# Heizstabsteuerung.net
KiCad netlist of a schematic drawn in EAGLE
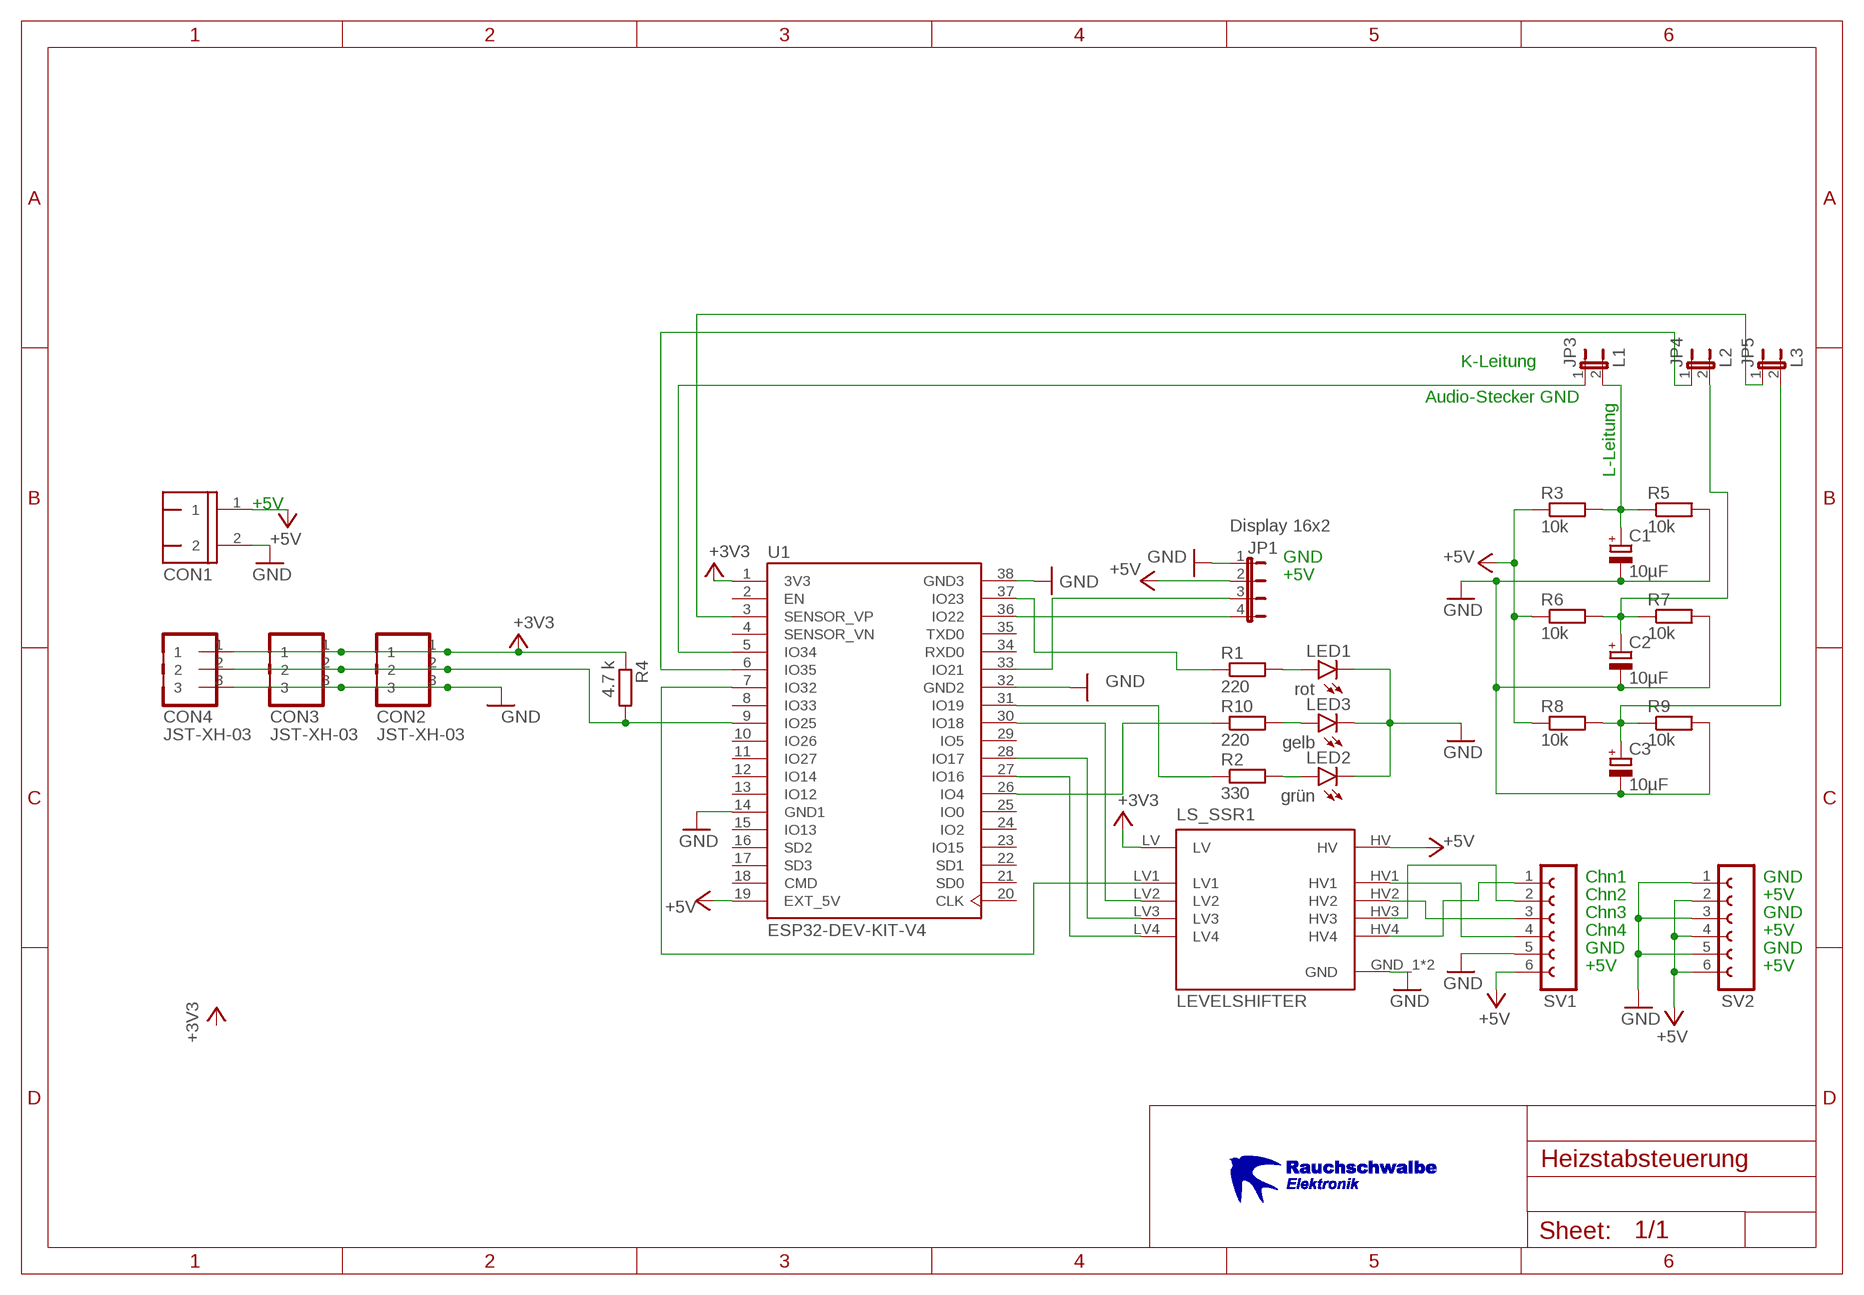
[diagram p0: schematic, sheet 1]

(export (version "E")
  (design (tool "Eeschema 10.0.6"))
  (components
    (comp (ref "C1")
      (value "10µF")
      (footprint "eagle-import:E2,5-5")
      (libsource (lib "eagle-import") (part "CPOL-EUE2.5-5"))
    )
    (comp (ref "C2")
      (value "10µF")
      (footprint "eagle-import:E2,5-5")
      (libsource (lib "eagle-import") (part "CPOL-EUE2.5-5"))
    )
    (comp (ref "C3")
      (value "10µF")
      (footprint "eagle-import:E2,5-5")
      (libsource (lib "eagle-import") (part "CPOL-EUE2.5-5"))
    )
    (comp (ref "CON1")
      (value "WAGO-500-2")
      (footprint "eagle-import:WAGO-500-2")
      (fields (field (name "MPN") "237-102"))
      (libsource (lib "eagle-import") (part "WAGO-500-2"))
    )
    (comp (ref "CON2")
      (value "JST-XH-03")
      (footprint "eagle-import:JST-XH-03")
      (libsource (lib "eagle-import") (part "JST-XH-03"))
    )
    (comp (ref "CON3")
      (value "JST-XH-03")
      (footprint "eagle-import:JST-XH-03")
      (libsource (lib "eagle-import") (part "JST-XH-03"))
    )
    (comp (ref "CON4")
      (value "JST-XH-03")
      (footprint "eagle-import:JST-XH-03")
      (libsource (lib "eagle-import") (part "JST-XH-03"))
    )
    (comp (ref "JP1")
      (value "Display 16x2")
      (footprint "eagle-import:JP4")
      (libsource (lib "eagle-import") (part "JP4E"))
    )
    (comp (ref "JP3")
      (value "L1")
      (footprint "eagle-import:JP1")
      (libsource (lib "eagle-import") (part "JP1E"))
    )
    (comp (ref "JP4")
      (value "L2")
      (footprint "eagle-import:JP1")
      (libsource (lib "eagle-import") (part "JP1E"))
    )
    (comp (ref "JP5")
      (value "L3")
      (footprint "eagle-import:JP1")
      (libsource (lib "eagle-import") (part "JP1E"))
    )
    (comp (ref "LED1")
      (value "rot")
      (footprint "eagle-import:LED3MM")
      (libsource (lib "eagle-import") (part "LED3MM"))
    )
    (comp (ref "LED2")
      (value "grün")
      (footprint "eagle-import:LED3MM")
      (libsource (lib "eagle-import") (part "LED3MM"))
    )
    (comp (ref "LED3")
      (value "gelb")
      (footprint "eagle-import:LED3MM")
      (libsource (lib "eagle-import") (part "LED3MM"))
    )
    (comp (ref "LS_SSR1")
      (value "LEVELSHIFTER")
      (footprint "eagle-import:LEVELSHIFTER")
      (fields (field (name "MF") "SparkFun") (field (name "MP") "BOB-12009"))
      (libsource (lib "eagle-import") (part "LEVELSHIFTER"))
    )
    (comp (ref "R1")
      (value "220")
      (footprint "eagle-import:0207_10")
      (libsource (lib "eagle-import") (part "R_10MM0207/10"))
    )
    (comp (ref "R2")
      (value "330")
      (footprint "eagle-import:0207_10")
      (libsource (lib "eagle-import") (part "R_10MM0207/10"))
    )
    (comp (ref "R3")
      (value "10k")
      (footprint "eagle-import:0207_10")
      (libsource (lib "eagle-import") (part "R_10MM0207/10"))
    )
    (comp (ref "R4")
      (value "4.7 k")
      (footprint "eagle-import:0207_10")
      (libsource (lib "eagle-import") (part "R_10MM0207/10"))
    )
    (comp (ref "R5")
      (value "10k")
      (footprint "eagle-import:0207_10")
      (libsource (lib "eagle-import") (part "R_10MM0207/10"))
    )
    (comp (ref "R6")
      (value "10k")
      (footprint "eagle-import:0207_10")
      (libsource (lib "eagle-import") (part "R_10MM0207/10"))
    )
    (comp (ref "R7")
      (value "10k")
      (footprint "eagle-import:0207_10")
      (libsource (lib "eagle-import") (part "R_10MM0207/10"))
    )
    (comp (ref "R8")
      (value "10k")
      (footprint "eagle-import:0207_10")
      (libsource (lib "eagle-import") (part "R_10MM0207/10"))
    )
    (comp (ref "R9")
      (value "10k")
      (footprint "eagle-import:0207_10")
      (libsource (lib "eagle-import") (part "R_10MM0207/10"))
    )
    (comp (ref "R10")
      (value "220")
      (footprint "eagle-import:0207_10")
      (libsource (lib "eagle-import") (part "R_10MM0207/10"))
    )
    (comp (ref "SV1")
      (value "FE06-1")
      (footprint "eagle-import:FE06")
      (libsource (lib "eagle-import") (part "FE06-1"))
    )
    (comp (ref "SV2")
      (value "FE06-1")
      (footprint "eagle-import:FE06")
      (libsource (lib "eagle-import") (part "FE06-1"))
    )
    (comp (ref "U$1")
      (value "LOGO_RAUCHSCHWALBE")
      (footprint "eagle-import:LOGO_RAUCHSCHWALBE")
      (libsource (lib "eagle-import") (part "LOGO_RAUCHSCHWALBE"))
    )
    (comp (ref "U1")
      (value "ESP32-DEV-KIT-V4")
      (footprint "eagle-import:ESP32-DEV-KIT-V4")
      (fields (field (name "MF") "Espressif Systems") (field (name "MP") "ESP32-DEVKITC"))
      (libsource (lib "eagle-import") (part "ESP32-DEV-KIT-V4"))
    )
  )
  (nets
    (net (code "1") (name "+3V3") (class "Default")
      (node (ref "CON2") (pin "1") (pinfunction "1_1") (pintype "passive"))
      (node (ref "CON3") (pin "1") (pinfunction "1_1") (pintype "passive"))
      (node (ref "CON4") (pin "1") (pinfunction "1_1") (pintype "passive"))
      (node (ref "LS_SSR1") (pin "LV") (pinfunction "LV_LV") (pintype "bidirectional"))
      (node (ref "R4") (pin "1") (pinfunction "1_1") (pintype "passive"))
      (node (ref "U1") (pin "1") (pinfunction "3V3_1") (pintype "power_in"))
    )
    (net (code "2") (name "+5V") (class "Default")
      (node (ref "CON1") (pin "1") (pinfunction "1_1") (pintype "passive"))
      (node (ref "JP1") (pin "2") (pinfunction "2_2") (pintype "passive"))
      (node (ref "LS_SSR1") (pin "HV") (pinfunction "HV_HV") (pintype "bidirectional"))
      (node (ref "R3") (pin "1") (pinfunction "1_1") (pintype "passive"))
      (node (ref "R6") (pin "1") (pinfunction "1_1") (pintype "passive"))
      (node (ref "R8") (pin "1") (pinfunction "1_1") (pintype "passive"))
      (node (ref "SV1") (pin "6") (pinfunction "6_6") (pintype "passive"))
      (node (ref "SV2") (pin "2") (pinfunction "2_2") (pintype "passive"))
      (node (ref "SV2") (pin "4") (pinfunction "4_4") (pintype "passive"))
      (node (ref "SV2") (pin "6") (pinfunction "6_6") (pintype "passive"))
      (node (ref "U1") (pin "19") (pinfunction "EXT_5V_19") (pintype "power_in"))
    )
    (net (code "3") (name "GND") (class "Default")
      (node (ref "C1") (pin "-") (pinfunction "-_-") (pintype "passive"))
      (node (ref "C2") (pin "-") (pinfunction "-_-") (pintype "passive"))
      (node (ref "C3") (pin "-") (pinfunction "-_-") (pintype "passive"))
      (node (ref "CON1") (pin "2") (pinfunction "2_2") (pintype "passive"))
      (node (ref "CON2") (pin "3") (pinfunction "3_3") (pintype "passive"))
      (node (ref "CON3") (pin "3") (pinfunction "3_3") (pintype "passive"))
      (node (ref "CON4") (pin "3") (pinfunction "3_3") (pintype "passive"))
      (node (ref "JP1") (pin "1") (pinfunction "1_1") (pintype "passive"))
      (node (ref "LED1") (pin "K") (pinfunction "C_K") (pintype "passive"))
      (node (ref "LED2") (pin "K") (pinfunction "C_K") (pintype "passive"))
      (node (ref "LED3") (pin "K") (pinfunction "C_K") (pintype "passive"))
      (node (ref "LS_SSR1") (pin "GND_1") (pinfunction "GND_GND_1") (pintype "power_in"))
      (node (ref "LS_SSR1") (pin "GND_2") (pinfunction "GND_GND_2") (pintype "power_in"))
      (node (ref "R5") (pin "2") (pinfunction "2_2") (pintype "passive"))
      (node (ref "R7") (pin "2") (pinfunction "2_2") (pintype "passive"))
      (node (ref "R9") (pin "2") (pinfunction "2_2") (pintype "passive"))
      (node (ref "SV1") (pin "5") (pinfunction "5_5") (pintype "passive"))
      (node (ref "SV2") (pin "1") (pinfunction "1_1") (pintype "passive"))
      (node (ref "SV2") (pin "3") (pinfunction "3_3") (pintype "passive"))
      (node (ref "SV2") (pin "5") (pinfunction "5_5") (pintype "passive"))
      (node (ref "U1") (pin "14") (pinfunction "GND1_14") (pintype "power_in"))
      (node (ref "U1") (pin "32") (pinfunction "GND2_32") (pintype "power_in"))
      (node (ref "U1") (pin "38") (pinfunction "GND3_38") (pintype "power_in"))
    )
    (net (code "4") (name "Net-(C1-Pad+)") (class "Default")
      (node (ref "C1") (pin "+") (pinfunction "+_+") (pintype "passive"))
      (node (ref "JP3") (pin "2") (pinfunction "2_2") (pintype "passive"))
      (node (ref "R3") (pin "2") (pinfunction "2_2") (pintype "passive"))
      (node (ref "R5") (pin "1") (pinfunction "1_1") (pintype "passive"))
    )
    (net (code "5") (name "Net-(C2-Pad+)") (class "Default")
      (node (ref "C2") (pin "+") (pinfunction "+_+") (pintype "passive"))
      (node (ref "JP4") (pin "2") (pinfunction "2_2") (pintype "passive"))
      (node (ref "R6") (pin "2") (pinfunction "2_2") (pintype "passive"))
      (node (ref "R7") (pin "1") (pinfunction "1_1") (pintype "passive"))
    )
    (net (code "6") (name "Net-(C3-Pad+)") (class "Default")
      (node (ref "C3") (pin "+") (pinfunction "+_+") (pintype "passive"))
      (node (ref "JP5") (pin "2") (pinfunction "2_2") (pintype "passive"))
      (node (ref "R8") (pin "2") (pinfunction "2_2") (pintype "passive"))
      (node (ref "R9") (pin "1") (pinfunction "1_1") (pintype "passive"))
    )
    (net (code "7") (name "Net-(LED1-PadA)") (class "Default")
      (node (ref "LED1") (pin "A") (pinfunction "A_A") (pintype "passive"))
      (node (ref "R1") (pin "2") (pinfunction "2_2") (pintype "passive"))
    )
    (net (code "8") (name "Net-(LED2-PadA)") (class "Default")
      (node (ref "LED2") (pin "A") (pinfunction "A_A") (pintype "passive"))
      (node (ref "R2") (pin "2") (pinfunction "2_2") (pintype "passive"))
    )
    (net (code "9") (name "Net-(LED3-PadA)") (class "Default")
      (node (ref "LED3") (pin "A") (pinfunction "A_A") (pintype "passive"))
      (node (ref "R10") (pin "2") (pinfunction "2_2") (pintype "passive"))
    )
    (net (code "10") (name "Net-(LS_SSR1-PadHV1)") (class "Default")
      (node (ref "LS_SSR1") (pin "HV1") (pinfunction "HV1_HV1") (pintype "bidirectional"))
      (node (ref "SV1") (pin "4") (pinfunction "4_4") (pintype "passive"))
    )
    (net (code "11") (name "Net-(LS_SSR1-PadHV2)") (class "Default")
      (node (ref "LS_SSR1") (pin "HV2") (pinfunction "HV2_HV2") (pintype "bidirectional"))
      (node (ref "SV1") (pin "3") (pinfunction "3_3") (pintype "passive"))
    )
    (net (code "12") (name "Net-(LS_SSR1-PadHV3)") (class "Default")
      (node (ref "LS_SSR1") (pin "HV3") (pinfunction "HV3_HV3") (pintype "bidirectional"))
      (node (ref "SV1") (pin "2") (pinfunction "2_2") (pintype "passive"))
    )
    (net (code "13") (name "Net-(LS_SSR1-PadHV4)") (class "Default")
      (node (ref "LS_SSR1") (pin "HV4") (pinfunction "HV4_HV4") (pintype "bidirectional"))
      (node (ref "SV1") (pin "1") (pinfunction "1_1") (pintype "passive"))
    )
    (net (code "14") (name "Net-(U1-IO4)") (class "Default")
      (node (ref "R10") (pin "1") (pinfunction "1_1") (pintype "passive"))
      (node (ref "U1") (pin "26") (pinfunction "IO4_26") (pintype "bidirectional"))
    )
    (net (code "15") (name "Net-(U1-IO16)") (class "Default")
      (node (ref "LS_SSR1") (pin "LV4") (pinfunction "LV4_LV4") (pintype "bidirectional"))
      (node (ref "U1") (pin "27") (pinfunction "IO16_27") (pintype "bidirectional"))
    )
    (net (code "16") (name "Net-(U1-IO17)") (class "Default")
      (node (ref "LS_SSR1") (pin "LV3") (pinfunction "LV3_LV3") (pintype "bidirectional"))
      (node (ref "U1") (pin "28") (pinfunction "IO17_28") (pintype "bidirectional"))
    )
    (net (code "17") (name "Net-(U1-IO18)") (class "Default")
      (node (ref "LS_SSR1") (pin "LV2") (pinfunction "LV2_LV2") (pintype "bidirectional"))
      (node (ref "U1") (pin "30") (pinfunction "IO18_30") (pintype "bidirectional"))
    )
    (net (code "18") (name "Net-(U1-IO19)") (class "Default")
      (node (ref "R2") (pin "1") (pinfunction "1_1") (pintype "passive"))
      (node (ref "U1") (pin "31") (pinfunction "IO19_31") (pintype "bidirectional"))
    )
    (net (code "19") (name "Net-(U1-IO21)") (class "Default")
      (node (ref "JP1") (pin "3") (pinfunction "3_3") (pintype "passive"))
      (node (ref "U1") (pin "33") (pinfunction "IO21_33") (pintype "bidirectional"))
    )
    (net (code "20") (name "Net-(U1-IO22)") (class "Default")
      (node (ref "JP1") (pin "4") (pinfunction "4_4") (pintype "passive"))
      (node (ref "U1") (pin "36") (pinfunction "IO22_36") (pintype "bidirectional"))
    )
    (net (code "21") (name "Net-(U1-IO23)") (class "Default")
      (node (ref "R1") (pin "1") (pinfunction "1_1") (pintype "passive"))
      (node (ref "U1") (pin "37") (pinfunction "IO23_37") (pintype "bidirectional"))
    )
    (net (code "22") (name "Net-(U1-IO25)") (class "Default")
      (node (ref "CON2") (pin "2") (pinfunction "2_2") (pintype "passive"))
      (node (ref "CON3") (pin "2") (pinfunction "2_2") (pintype "passive"))
      (node (ref "CON4") (pin "2") (pinfunction "2_2") (pintype "passive"))
      (node (ref "R4") (pin "2") (pinfunction "2_2") (pintype "passive"))
      (node (ref "U1") (pin "9") (pinfunction "IO25_9") (pintype "bidirectional"))
    )
    (net (code "23") (name "Net-(U1-IO32)") (class "Default")
      (node (ref "LS_SSR1") (pin "LV1") (pinfunction "LV1_LV1") (pintype "bidirectional"))
      (node (ref "U1") (pin "7") (pinfunction "IO32_7") (pintype "bidirectional"))
    )
    (net (code "24") (name "Net-(U1-IO34)") (class "Default")
      (node (ref "JP3") (pin "1") (pinfunction "1_1") (pintype "passive"))
      (node (ref "U1") (pin "5") (pinfunction "IO34_5") (pintype "bidirectional"))
    )
    (net (code "25") (name "Net-(U1-IO35)") (class "Default")
      (node (ref "JP4") (pin "1") (pinfunction "1_1") (pintype "passive"))
      (node (ref "U1") (pin "6") (pinfunction "IO35_6") (pintype "bidirectional"))
    )
    (net (code "26") (name "Net-(U1-SENSOR_VP)") (class "Default")
      (node (ref "JP5") (pin "1") (pinfunction "1_1") (pintype "passive"))
      (node (ref "U1") (pin "3") (pinfunction "SENSOR_VP_3") (pintype "input"))
    )
    (net (code "27") (name "unconnected-(U1-CLK-Pad20)") (class "Default")
      (node (ref "U1") (pin "20") (pinfunction "CLK_20") (pintype "input"))
    )
    (net (code "28") (name "unconnected-(U1-CMD-Pad18)") (class "Default")
      (node (ref "U1") (pin "18") (pinfunction "CMD_18") (pintype "bidirectional"))
    )
    (net (code "29") (name "unconnected-(U1-EN-Pad2)") (class "Default")
      (node (ref "U1") (pin "2") (pinfunction "EN_2") (pintype "input"))
    )
    (net (code "30") (name "unconnected-(U1-IO0-Pad25)") (class "Default")
      (node (ref "U1") (pin "25") (pinfunction "IO0_25") (pintype "bidirectional"))
    )
    (net (code "31") (name "unconnected-(U1-IO2-Pad24)") (class "Default")
      (node (ref "U1") (pin "24") (pinfunction "IO2_24") (pintype "bidirectional"))
    )
    (net (code "32") (name "unconnected-(U1-IO5-Pad29)") (class "Default")
      (node (ref "U1") (pin "29") (pinfunction "IO5_29") (pintype "bidirectional"))
    )
    (net (code "33") (name "unconnected-(U1-IO12-Pad13)") (class "Default")
      (node (ref "U1") (pin "13") (pinfunction "IO12_13") (pintype "bidirectional"))
    )
    (net (code "34") (name "unconnected-(U1-IO13-Pad15)") (class "Default")
      (node (ref "U1") (pin "15") (pinfunction "IO13_15") (pintype "bidirectional"))
    )
    (net (code "35") (name "unconnected-(U1-IO14-Pad12)") (class "Default")
      (node (ref "U1") (pin "12") (pinfunction "IO14_12") (pintype "bidirectional"))
    )
    (net (code "36") (name "unconnected-(U1-IO15-Pad23)") (class "Default")
      (node (ref "U1") (pin "23") (pinfunction "IO15_23") (pintype "bidirectional"))
    )
    (net (code "37") (name "unconnected-(U1-IO26-Pad10)") (class "Default")
      (node (ref "U1") (pin "10") (pinfunction "IO26_10") (pintype "bidirectional"))
    )
    (net (code "38") (name "unconnected-(U1-IO27-Pad11)") (class "Default")
      (node (ref "U1") (pin "11") (pinfunction "IO27_11") (pintype "bidirectional"))
    )
    (net (code "39") (name "unconnected-(U1-IO33-Pad8)") (class "Default")
      (node (ref "U1") (pin "8") (pinfunction "IO33_8") (pintype "bidirectional"))
    )
    (net (code "40") (name "unconnected-(U1-RXD0-Pad34)") (class "Default")
      (node (ref "U1") (pin "34") (pinfunction "RXD0_34") (pintype "input"))
    )
    (net (code "41") (name "unconnected-(U1-SD0-Pad21)") (class "Default")
      (node (ref "U1") (pin "21") (pinfunction "SD0_21") (pintype "bidirectional"))
    )
    (net (code "42") (name "unconnected-(U1-SD1-Pad22)") (class "Default")
      (node (ref "U1") (pin "22") (pinfunction "SD1_22") (pintype "bidirectional"))
    )
    (net (code "43") (name "unconnected-(U1-SD2-Pad16)") (class "Default")
      (node (ref "U1") (pin "16") (pinfunction "SD2_16") (pintype "bidirectional"))
    )
    (net (code "44") (name "unconnected-(U1-SD3-Pad17)") (class "Default")
      (node (ref "U1") (pin "17") (pinfunction "SD3_17") (pintype "bidirectional"))
    )
    (net (code "45") (name "unconnected-(U1-SENSOR_VN-Pad4)") (class "Default")
      (node (ref "U1") (pin "4") (pinfunction "SENSOR_VN_4") (pintype "input"))
    )
    (net (code "46") (name "unconnected-(U1-TXD0-Pad35)") (class "Default")
      (node (ref "U1") (pin "35") (pinfunction "TXD0_35") (pintype "output"))
    )
  )
)
